# LEDs_Switches.net
KiCad netlist of a schematic drawn in Altium Designer
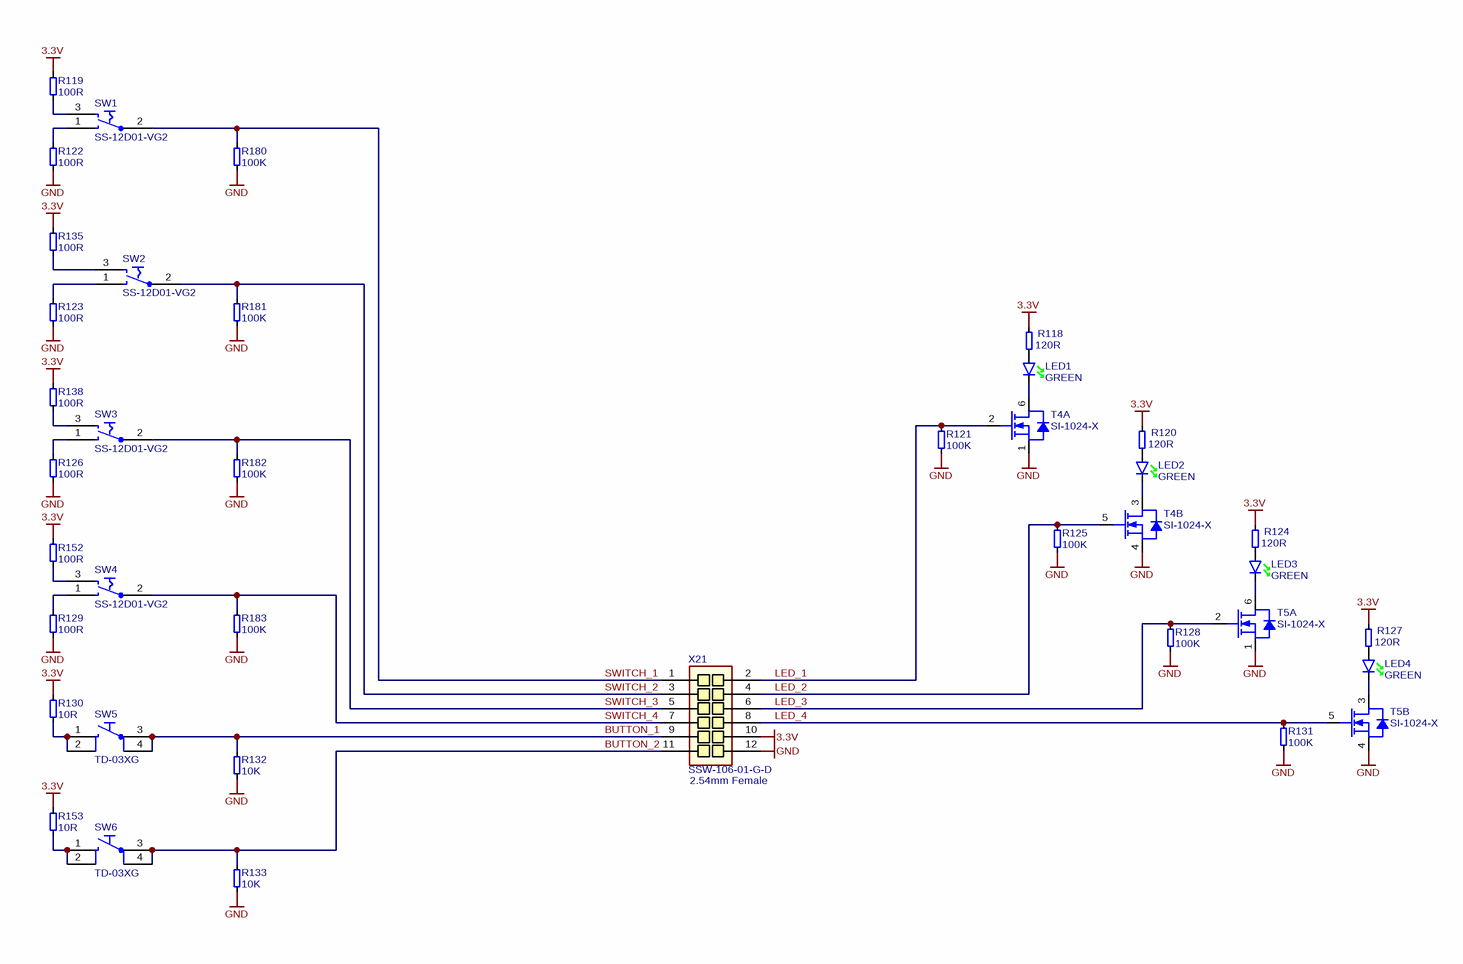
[diagram p0: LEDs_Switches.SchDoc]

(export (version "E")
  (design (tool "Eeschema 10.0.6"))
  (components
    (comp (ref "LED1")
      (value "LG T670-K1L2-1")
      (footprint "T_Osram_T670_GREEN")
      (description "LED green Osram LG T670-K1L2-1")
      (fields (field (name "COLOR") "GREEN"))
      (libsource (lib "Evaluation Board") (part "LED-Osram-T670-K1L2-1"))
    )
    (comp (ref "LED2")
      (value "LG T670-K1L2-1")
      (footprint "T_Osram_T670_GREEN")
      (description "LED green Osram LG T670-K1L2-1")
      (fields (field (name "COLOR") "GREEN"))
      (libsource (lib "Evaluation Board") (part "LED-Osram-T670-K1L2-1"))
    )
    (comp (ref "LED3")
      (value "LG T670-K1L2-1")
      (footprint "T_Osram_T670_GREEN")
      (description "LED green Osram LG T670-K1L2-1")
      (fields (field (name "COLOR") "GREEN"))
      (libsource (lib "Evaluation Board") (part "LED-Osram-T670-K1L2-1"))
    )
    (comp (ref "LED4")
      (value "LG T670-K1L2-1")
      (footprint "T_Osram_T670_GREEN")
      (description "LED green Osram LG T670-K1L2-1")
      (fields (field (name "COLOR") "GREEN"))
      (libsource (lib "Evaluation Board") (part "LED-Osram-T670-K1L2-1"))
    )
    (comp (ref "R118")
      (value "120R")
      (footprint "T_RESC0603X30N")
      (description "Resistor 120 ohm 63mW 5% 0603")
      (fields (field (name "TOLERANCE") "5%"))
      (libsource (lib "Evaluation Board") (part "R-120R-63mW-5%-0603"))
    )
    (comp (ref "R119")
      (value "100R")
      (footprint "T_RESC0603X30N")
      (description "Resistor 100 ohm 63mW 5% 0603")
      (fields (field (name "TOLERANCE") "5%"))
      (libsource (lib "Evaluation Board") (part "R-100R-63mW-5%-0603"))
    )
    (comp (ref "R120")
      (value "120R")
      (footprint "T_RESC0603X30N")
      (description "Resistor 120 ohm 63mW 5% 0603")
      (fields (field (name "TOLERANCE") "5%"))
      (libsource (lib "Evaluation Board") (part "R-120R-63mW-5%-0603"))
    )
    (comp (ref "R121")
      (value "100K")
      (footprint "T_RESC0603X30N")
      (description "Resistor 100 Kohm 63mW 5% 0603")
      (fields (field (name "TOLERANCE") "5%"))
      (libsource (lib "Evaluation Board") (part "R-100KR-63mW-5%-0603"))
    )
    (comp (ref "R122")
      (value "100R")
      (footprint "T_RESC0603X30N")
      (description "Resistor 100 ohm 63mW 5% 0603")
      (fields (field (name "TOLERANCE") "5%"))
      (libsource (lib "Evaluation Board") (part "R-100R-63mW-5%-0603"))
    )
    (comp (ref "R123")
      (value "100R")
      (footprint "T_RESC0603X30N")
      (description "Resistor 100 ohm 63mW 5% 0603")
      (fields (field (name "TOLERANCE") "5%"))
      (libsource (lib "Evaluation Board") (part "R-100R-63mW-5%-0603"))
    )
    (comp (ref "R124")
      (value "120R")
      (footprint "T_RESC0603X30N")
      (description "Resistor 120 ohm 63mW 5% 0603")
      (fields (field (name "TOLERANCE") "5%"))
      (libsource (lib "Evaluation Board") (part "R-120R-63mW-5%-0603"))
    )
    (comp (ref "R125")
      (value "100K")
      (footprint "T_RESC0603X30N")
      (description "Resistor 100 Kohm 63mW 5% 0603")
      (fields (field (name "TOLERANCE") "5%"))
      (libsource (lib "Evaluation Board") (part "R-100KR-63mW-5%-0603"))
    )
    (comp (ref "R126")
      (value "100R")
      (footprint "T_RESC0603X30N")
      (description "Resistor 100 ohm 63mW 5% 0603")
      (fields (field (name "TOLERANCE") "5%"))
      (libsource (lib "Evaluation Board") (part "R-100R-63mW-5%-0603"))
    )
    (comp (ref "R127")
      (value "120R")
      (footprint "T_RESC0603X30N")
      (description "Resistor 120 ohm 63mW 5% 0603")
      (fields (field (name "TOLERANCE") "5%"))
      (libsource (lib "Evaluation Board") (part "R-120R-63mW-5%-0603"))
    )
    (comp (ref "R128")
      (value "100K")
      (footprint "T_RESC0603X30N")
      (description "Resistor 100 Kohm 63mW 5% 0603")
      (fields (field (name "TOLERANCE") "5%"))
      (libsource (lib "Evaluation Board") (part "R-100KR-63mW-5%-0603"))
    )
    (comp (ref "R129")
      (value "100R")
      (footprint "T_RESC0603X30N")
      (description "Resistor 100 ohm 63mW 5% 0603")
      (fields (field (name "TOLERANCE") "5%"))
      (libsource (lib "Evaluation Board") (part "R-100R-63mW-5%-0603"))
    )
    (comp (ref "R130")
      (value "10R")
      (footprint "T_RESC0603X30N")
      (description "Resistor 10 ohm 63mW 5% 0603")
      (fields (field (name "TOLERANCE") "5%"))
      (libsource (lib "Evaluation Board") (part "R-10R-63mW-5%-0603"))
    )
    (comp (ref "R131")
      (value "100K")
      (footprint "T_RESC0603X30N")
      (description "Resistor 100 Kohm 63mW 5% 0603")
      (fields (field (name "TOLERANCE") "5%"))
      (libsource (lib "Evaluation Board") (part "R-100KR-63mW-5%-0603"))
    )
    (comp (ref "R132")
      (value "10K")
      (footprint "T_RESC0603X30N")
      (description "Resistor 10 Kohm 63mW 5% 0603")
      (fields (field (name "TOLERANCE") "5%"))
      (libsource (lib "Evaluation Board") (part "R-10KR-63mW-5%-0603"))
    )
    (comp (ref "R133")
      (value "10K")
      (footprint "T_RESC0603X30N")
      (description "Resistor 10 Kohm 63mW 5% 0603")
      (fields (field (name "TOLERANCE") "5%"))
      (libsource (lib "Evaluation Board") (part "R-10KR-63mW-5%-0603"))
    )
    (comp (ref "R135")
      (value "100R")
      (footprint "T_RESC0603X30N")
      (description "Resistor 100 ohm 63mW 5% 0603")
      (fields (field (name "TOLERANCE") "5%"))
      (libsource (lib "Evaluation Board") (part "R-100R-63mW-5%-0603"))
    )
    (comp (ref "R138")
      (value "100R")
      (footprint "T_RESC0603X30N")
      (description "Resistor 100 ohm 63mW 5% 0603")
      (fields (field (name "TOLERANCE") "5%"))
      (libsource (lib "Evaluation Board") (part "R-100R-63mW-5%-0603"))
    )
    (comp (ref "R152")
      (value "100R")
      (footprint "T_RESC0603X30N")
      (description "Resistor 100 ohm 63mW 5% 0603")
      (fields (field (name "TOLERANCE") "5%"))
      (libsource (lib "Evaluation Board") (part "R-100R-63mW-5%-0603"))
    )
    (comp (ref "R153")
      (value "10R")
      (footprint "T_RESC0603X30N")
      (description "Resistor 10 ohm 63mW 5% 0603")
      (fields (field (name "TOLERANCE") "5%"))
      (libsource (lib "Evaluation Board") (part "R-10R-63mW-5%-0603"))
    )
    (comp (ref "R180")
      (value "100K")
      (footprint "T_RESC0603X30N")
      (description "Resistor 100 Kohm 63mW 5% 0603")
      (fields (field (name "TOLERANCE") "5%"))
      (libsource (lib "Evaluation Board") (part "R-100KR-63mW-5%-0603"))
    )
    (comp (ref "R181")
      (value "100K")
      (footprint "T_RESC0603X30N")
      (description "Resistor 100 Kohm 63mW 5% 0603")
      (fields (field (name "TOLERANCE") "5%"))
      (libsource (lib "Evaluation Board") (part "R-100KR-63mW-5%-0603"))
    )
    (comp (ref "R182")
      (value "100K")
      (footprint "T_RESC0603X30N")
      (description "Resistor 100 Kohm 63mW 5% 0603")
      (fields (field (name "TOLERANCE") "5%"))
      (libsource (lib "Evaluation Board") (part "R-100KR-63mW-5%-0603"))
    )
    (comp (ref "R183")
      (value "100K")
      (footprint "T_RESC0603X30N")
      (description "Resistor 100 Kohm 63mW 5% 0603")
      (fields (field (name "TOLERANCE") "5%"))
      (libsource (lib "Evaluation Board") (part "R-100KR-63mW-5%-0603"))
    )
    (comp (ref "SW1")
      (value "SS-12D01-VG2")
      (footprint "T_See-Plus_SS-12D01-VG2")
      (description "Switch")
      (libsource (lib "Evaluation Board") (part "SW-See-Plus-SS-12D01-VG2"))
    )
    (comp (ref "SW2")
      (value "SS-12D01-VG2")
      (footprint "T_See-Plus_SS-12D01-VG2")
      (description "Switch")
      (libsource (lib "Evaluation Board") (part "SW-See-Plus-SS-12D01-VG2"))
    )
    (comp (ref "SW3")
      (value "SS-12D01-VG2")
      (footprint "T_See-Plus_SS-12D01-VG2")
      (description "Switch")
      (libsource (lib "Evaluation Board") (part "SW-See-Plus-SS-12D01-VG2"))
    )
    (comp (ref "SW4")
      (value "SS-12D01-VG2")
      (footprint "T_See-Plus_SS-12D01-VG2")
      (description "Switch")
      (libsource (lib "Evaluation Board") (part "SW-See-Plus-SS-12D01-VG2"))
    )
    (comp (ref "SW5")
      (value "TD-03XG")
      (footprint "T_WMF_TD-03XG")
      (description "Switch")
      (libsource (lib "Evaluation Board") (part "SW-WMF-TD-03XG"))
    )
    (comp (ref "SW6")
      (value "TD-03XG")
      (footprint "T_WMF_TD-03XG")
      (description "Switch")
      (libsource (lib "Evaluation Board") (part "SW-WMF-TD-03XG"))
    )
    (comp (ref "T4")
      (value "T-Vishay-SI-1024X-N")
      (footprint "SOTFL50P160X60-6N")
      (description "Dual N-Channel 20V (D-S)  MOSFET")
      (fields (field (name "MANUFACTURER PART NO.") "SI-1024-X"))
      (libsource (lib "Evaluation Board") (part "T-Vishay-SI-1024X-N"))
    )
    (comp (ref "T5")
      (value "T-Vishay-SI-1024X-N")
      (footprint "SOTFL50P160X60-6N")
      (description "Dual N-Channel 20V (D-S)  MOSFET")
      (fields (field (name "MANUFACTURER PART NO.") "SI-1024-X"))
      (libsource (lib "Evaluation Board") (part "T-Vishay-SI-1024X-N"))
    )
    (comp (ref "X21")
      (value "SSW-106-01-G-D")
      (footprint "T_Samtec_SSW-106-01-G-D")
      (description "Header Female, 2x6 Pins, 2.54 mm pitch")
      (fields (field (name "MANUFACTURER PART NO.") "SSW-106-01-G-D"))
      (libsource (lib "Evaluation Board") (part "CON-Samtec-SSW-106-01-G-D"))
    )
  )
  (nets
    (net (code "1") (name "/BUTTON_1") (class "Default")
      (node (ref "R132") (pin "2") (pinfunction "2_2") (pintype "passive"))
      (node (ref "SW5") (pin "3") (pinfunction "3_3") (pintype "passive"))
      (node (ref "SW5") (pin "4") (pinfunction "4_4") (pintype "passive"))
      (node (ref "X21") (pin "9") (pinfunction "9_9") (pintype "passive"))
    )
    (net (code "2") (name "/BUTTON_2") (class "Default")
      (node (ref "R133") (pin "2") (pinfunction "2_2") (pintype "passive"))
      (node (ref "SW6") (pin "3") (pinfunction "3_3") (pintype "passive"))
      (node (ref "SW6") (pin "4") (pinfunction "4_4") (pintype "passive"))
      (node (ref "X21") (pin "11") (pinfunction "11_11") (pintype "passive"))
    )
    (net (code "3") (name "/LED_1") (class "Default")
      (node (ref "R121") (pin "2") (pinfunction "2_2") (pintype "passive"))
      (node (ref "T4") (pin "2") (pinfunction "G_2") (pintype "passive"))
      (node (ref "X21") (pin "2") (pinfunction "2_2") (pintype "passive"))
    )
    (net (code "4") (name "/LED_2") (class "Default")
      (node (ref "R125") (pin "2") (pinfunction "2_2") (pintype "passive"))
      (node (ref "T4") (pin "5") (pinfunction "G_5") (pintype "passive"))
      (node (ref "X21") (pin "4") (pinfunction "4_4") (pintype "passive"))
    )
    (net (code "5") (name "/LED_3") (class "Default")
      (node (ref "R128") (pin "2") (pinfunction "2_2") (pintype "passive"))
      (node (ref "T5") (pin "2") (pinfunction "G_2") (pintype "passive"))
      (node (ref "X21") (pin "6") (pinfunction "6_6") (pintype "passive"))
    )
    (net (code "6") (name "/LED_4") (class "Default")
      (node (ref "R131") (pin "2") (pinfunction "2_2") (pintype "passive"))
      (node (ref "T5") (pin "5") (pinfunction "G_5") (pintype "passive"))
      (node (ref "X21") (pin "8") (pinfunction "8_8") (pintype "passive"))
    )
    (net (code "7") (name "/SWITCH_1") (class "Default")
      (node (ref "R180") (pin "2") (pinfunction "2_2") (pintype "passive"))
      (node (ref "SW1") (pin "2") (pinfunction "2_2") (pintype "passive"))
      (node (ref "X21") (pin "1") (pinfunction "1_1") (pintype "passive"))
    )
    (net (code "8") (name "/SWITCH_2") (class "Default")
      (node (ref "R181") (pin "2") (pinfunction "2_2") (pintype "passive"))
      (node (ref "SW2") (pin "2") (pinfunction "2_2") (pintype "passive"))
      (node (ref "X21") (pin "3") (pinfunction "3_3") (pintype "passive"))
    )
    (net (code "9") (name "/SWITCH_3") (class "Default")
      (node (ref "R182") (pin "2") (pinfunction "2_2") (pintype "passive"))
      (node (ref "SW3") (pin "2") (pinfunction "2_2") (pintype "passive"))
      (node (ref "X21") (pin "5") (pinfunction "5_5") (pintype "passive"))
    )
    (net (code "10") (name "/SWITCH_4") (class "Default")
      (node (ref "R183") (pin "2") (pinfunction "2_2") (pintype "passive"))
      (node (ref "SW4") (pin "2") (pinfunction "2_2") (pintype "passive"))
      (node (ref "X21") (pin "7") (pinfunction "7_7") (pintype "passive"))
    )
    (net (code "11") (name "3.3V") (class "Default")
      (node (ref "R118") (pin "2") (pinfunction "2_2") (pintype "passive"))
      (node (ref "R119") (pin "2") (pinfunction "2_2") (pintype "passive"))
      (node (ref "R120") (pin "2") (pinfunction "2_2") (pintype "passive"))
      (node (ref "R124") (pin "2") (pinfunction "2_2") (pintype "passive"))
      (node (ref "R127") (pin "2") (pinfunction "2_2") (pintype "passive"))
      (node (ref "R130") (pin "2") (pinfunction "2_2") (pintype "passive"))
      (node (ref "R135") (pin "2") (pinfunction "2_2") (pintype "passive"))
      (node (ref "R138") (pin "2") (pinfunction "2_2") (pintype "passive"))
      (node (ref "R152") (pin "2") (pinfunction "2_2") (pintype "passive"))
      (node (ref "R153") (pin "2") (pinfunction "2_2") (pintype "passive"))
      (node (ref "X21") (pin "10") (pinfunction "10_10") (pintype "passive"))
    )
    (net (code "12") (name "GND") (class "Default")
      (node (ref "R121") (pin "1") (pinfunction "1_1") (pintype "passive"))
      (node (ref "R122") (pin "1") (pinfunction "1_1") (pintype "passive"))
      (node (ref "R123") (pin "1") (pinfunction "1_1") (pintype "passive"))
      (node (ref "R125") (pin "1") (pinfunction "1_1") (pintype "passive"))
      (node (ref "R126") (pin "1") (pinfunction "1_1") (pintype "passive"))
      (node (ref "R128") (pin "1") (pinfunction "1_1") (pintype "passive"))
      (node (ref "R129") (pin "1") (pinfunction "1_1") (pintype "passive"))
      (node (ref "R131") (pin "1") (pinfunction "1_1") (pintype "passive"))
      (node (ref "R132") (pin "1") (pinfunction "1_1") (pintype "passive"))
      (node (ref "R133") (pin "1") (pinfunction "1_1") (pintype "passive"))
      (node (ref "R180") (pin "1") (pinfunction "1_1") (pintype "passive"))
      (node (ref "R181") (pin "1") (pinfunction "1_1") (pintype "passive"))
      (node (ref "R182") (pin "1") (pinfunction "1_1") (pintype "passive"))
      (node (ref "R183") (pin "1") (pinfunction "1_1") (pintype "passive"))
      (node (ref "T4") (pin "1") (pinfunction "S_1") (pintype "passive"))
      (node (ref "T4") (pin "4") (pinfunction "S_4") (pintype "passive"))
      (node (ref "T5") (pin "1") (pinfunction "S_1") (pintype "passive"))
      (node (ref "T5") (pin "4") (pinfunction "S_4") (pintype "passive"))
      (node (ref "X21") (pin "12") (pinfunction "12_12") (pintype "passive"))
    )
    (net (code "13") (name "Net-(LED1-PadA)") (class "Default")
      (node (ref "LED1") (pin "A") (pinfunction "A_A") (pintype "passive"))
      (node (ref "R118") (pin "1") (pinfunction "1_1") (pintype "passive"))
    )
    (net (code "14") (name "Net-(LED2-PadA)") (class "Default")
      (node (ref "LED2") (pin "A") (pinfunction "A_A") (pintype "passive"))
      (node (ref "R120") (pin "1") (pinfunction "1_1") (pintype "passive"))
    )
    (net (code "15") (name "Net-(LED3-PadA)") (class "Default")
      (node (ref "LED3") (pin "A") (pinfunction "A_A") (pintype "passive"))
      (node (ref "R124") (pin "1") (pinfunction "1_1") (pintype "passive"))
    )
    (net (code "16") (name "Net-(LED4-PadA)") (class "Default")
      (node (ref "LED4") (pin "A") (pinfunction "A_A") (pintype "passive"))
      (node (ref "R127") (pin "1") (pinfunction "1_1") (pintype "passive"))
    )
    (net (code "17") (name "Net-(R119-Pad1)") (class "Default")
      (node (ref "R119") (pin "1") (pinfunction "1_1") (pintype "passive"))
      (node (ref "SW1") (pin "3") (pinfunction "3_3") (pintype "passive"))
    )
    (net (code "18") (name "Net-(R122-Pad2)") (class "Default")
      (node (ref "R122") (pin "2") (pinfunction "2_2") (pintype "passive"))
      (node (ref "SW1") (pin "1") (pinfunction "1_1") (pintype "passive"))
    )
    (net (code "19") (name "Net-(R123-Pad2)") (class "Default")
      (node (ref "R123") (pin "2") (pinfunction "2_2") (pintype "passive"))
      (node (ref "SW2") (pin "1") (pinfunction "1_1") (pintype "passive"))
    )
    (net (code "20") (name "Net-(R126-Pad2)") (class "Default")
      (node (ref "R126") (pin "2") (pinfunction "2_2") (pintype "passive"))
      (node (ref "SW3") (pin "1") (pinfunction "1_1") (pintype "passive"))
    )
    (net (code "21") (name "Net-(R129-Pad2)") (class "Default")
      (node (ref "R129") (pin "2") (pinfunction "2_2") (pintype "passive"))
      (node (ref "SW4") (pin "1") (pinfunction "1_1") (pintype "passive"))
    )
    (net (code "22") (name "Net-(R130-Pad1)") (class "Default")
      (node (ref "R130") (pin "1") (pinfunction "1_1") (pintype "passive"))
      (node (ref "SW5") (pin "1") (pinfunction "1_1") (pintype "passive"))
      (node (ref "SW5") (pin "2") (pinfunction "2_2") (pintype "passive"))
    )
    (net (code "23") (name "Net-(R135-Pad1)") (class "Default")
      (node (ref "R135") (pin "1") (pinfunction "1_1") (pintype "passive"))
      (node (ref "SW2") (pin "3") (pinfunction "3_3") (pintype "passive"))
    )
    (net (code "24") (name "Net-(R138-Pad1)") (class "Default")
      (node (ref "R138") (pin "1") (pinfunction "1_1") (pintype "passive"))
      (node (ref "SW3") (pin "3") (pinfunction "3_3") (pintype "passive"))
    )
    (net (code "25") (name "Net-(R152-Pad1)") (class "Default")
      (node (ref "R152") (pin "1") (pinfunction "1_1") (pintype "passive"))
      (node (ref "SW4") (pin "3") (pinfunction "3_3") (pintype "passive"))
    )
    (net (code "26") (name "Net-(R153-Pad1)") (class "Default")
      (node (ref "R153") (pin "1") (pinfunction "1_1") (pintype "passive"))
      (node (ref "SW6") (pin "1") (pinfunction "1_1") (pintype "passive"))
      (node (ref "SW6") (pin "2") (pinfunction "2_2") (pintype "passive"))
    )
    (net (code "27") (name "Net-(T4A-D)") (class "Default")
      (node (ref "LED1") (pin "K") (pinfunction "K_K") (pintype "passive"))
      (node (ref "T4") (pin "6") (pinfunction "D_6") (pintype "passive"))
    )
    (net (code "28") (name "Net-(T4B-D)") (class "Default")
      (node (ref "LED2") (pin "K") (pinfunction "K_K") (pintype "passive"))
      (node (ref "T4") (pin "3") (pinfunction "D_3") (pintype "passive"))
    )
    (net (code "29") (name "Net-(T5A-D)") (class "Default")
      (node (ref "LED3") (pin "K") (pinfunction "K_K") (pintype "passive"))
      (node (ref "T5") (pin "6") (pinfunction "D_6") (pintype "passive"))
    )
    (net (code "30") (name "Net-(T5B-D)") (class "Default")
      (node (ref "LED4") (pin "K") (pinfunction "K_K") (pintype "passive"))
      (node (ref "T5") (pin "3") (pinfunction "D_3") (pintype "passive"))
    )
  )
)
